# dcy_vca_v1_0_1.net
KiCad netlist of a schematic drawn in EAGLE
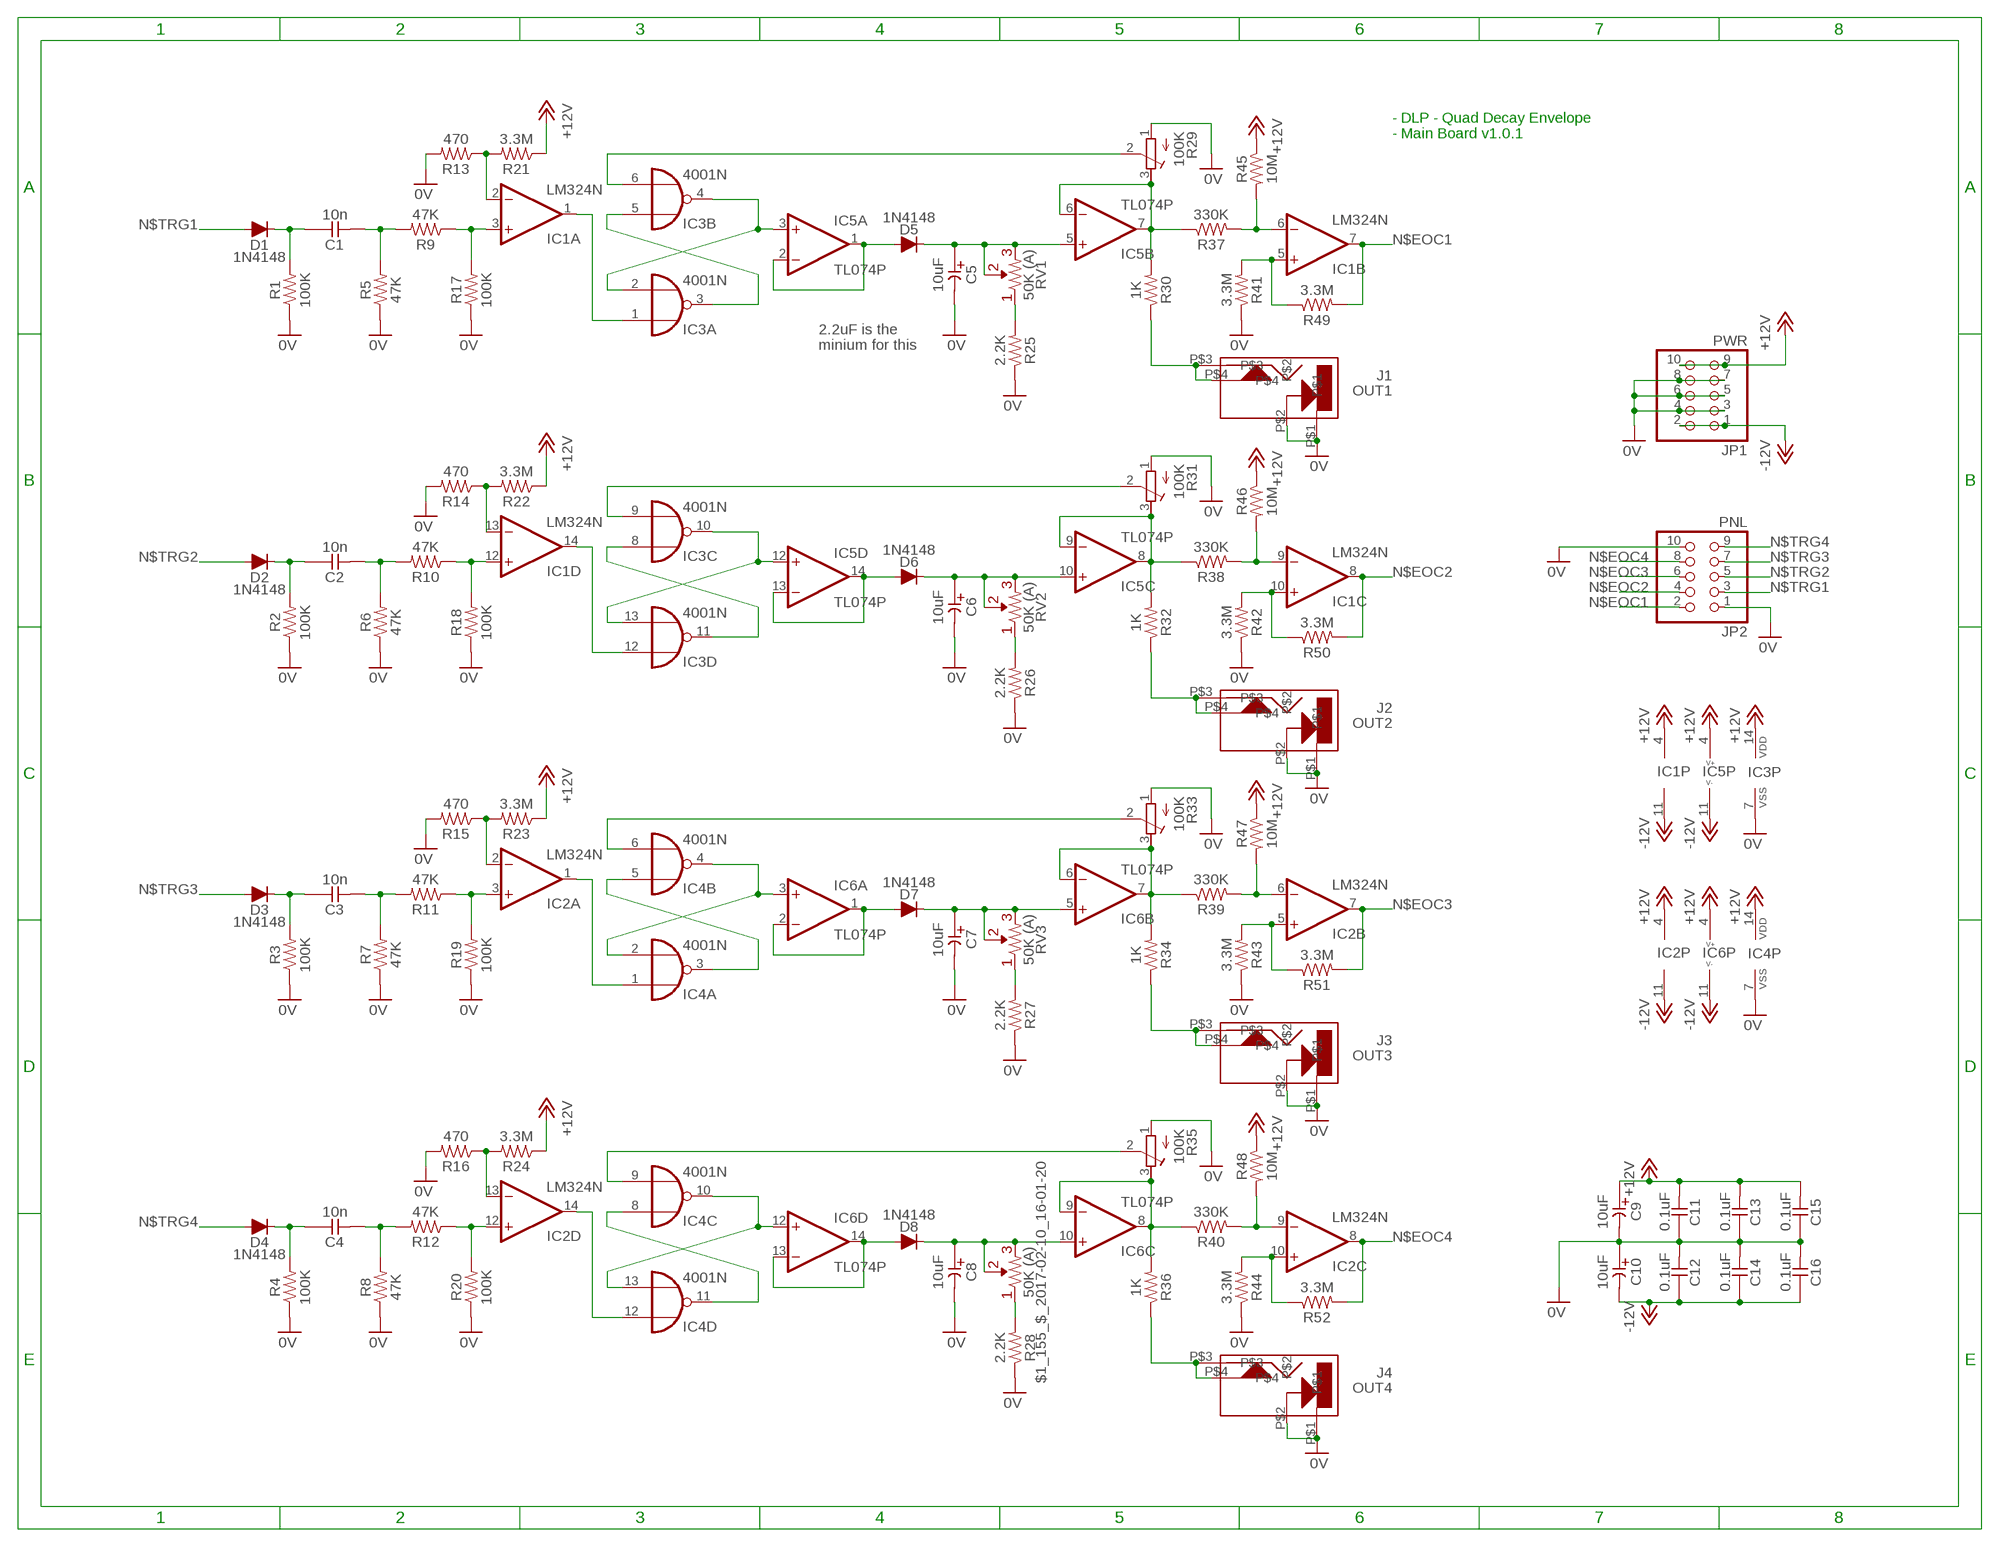
[diagram p0: schematic, sheet 1]

(export (version "E")
  (design (tool "Eeschema 10.0.6"))
  (components
    (comp (ref "$1_155_$_2017-02-10_16-01-20")
      (value "50K (A)")
      (footprint "eagle-import:R-VAR")
      (libsource (lib "eagle-import") (part "R-VAR"))
    )
    (comp (ref "C1")
      (value "10n")
      (footprint "eagle-import:C025-024X044")
      (libsource (lib "eagle-import") (part "CC-US025-024X044"))
    )
    (comp (ref "C2")
      (value "10n")
      (footprint "eagle-import:C025-024X044")
      (libsource (lib "eagle-import") (part "CC-US025-024X044"))
    )
    (comp (ref "C3")
      (value "10n")
      (footprint "eagle-import:C025-024X044")
      (libsource (lib "eagle-import") (part "CC-US025-024X044"))
    )
    (comp (ref "C4")
      (value "10n")
      (footprint "eagle-import:C025-024X044")
      (libsource (lib "eagle-import") (part "CC-US025-024X044"))
    )
    (comp (ref "C5")
      (value "10uF")
      (footprint "eagle-import:E2-5")
      (libsource (lib "eagle-import") (part "CE-USE2-5"))
    )
    (comp (ref "C6")
      (value "10uF")
      (footprint "eagle-import:E2-5")
      (libsource (lib "eagle-import") (part "CE-USE2-5"))
    )
    (comp (ref "C7")
      (value "10uF")
      (footprint "eagle-import:E2-5")
      (libsource (lib "eagle-import") (part "CE-USE2-5"))
    )
    (comp (ref "C8")
      (value "10uF")
      (footprint "eagle-import:E2-5")
      (libsource (lib "eagle-import") (part "CE-USE2-5"))
    )
    (comp (ref "C9")
      (value "10uF")
      (footprint "eagle-import:E2-5")
      (libsource (lib "eagle-import") (part "CE-USE2-5"))
    )
    (comp (ref "C10")
      (value "10uF")
      (footprint "eagle-import:E2-5")
      (libsource (lib "eagle-import") (part "CE-USE2-5"))
    )
    (comp (ref "C11")
      (value "0.1uF")
      (footprint "eagle-import:C025-024X044")
      (libsource (lib "eagle-import") (part "CC-US025-024X044"))
    )
    (comp (ref "C12")
      (value "0.1uF")
      (footprint "eagle-import:C025-024X044")
      (libsource (lib "eagle-import") (part "CC-US025-024X044"))
    )
    (comp (ref "C13")
      (value "0.1uF")
      (footprint "eagle-import:C025-024X044")
      (libsource (lib "eagle-import") (part "CC-US025-024X044"))
    )
    (comp (ref "C14")
      (value "0.1uF")
      (footprint "eagle-import:C025-024X044")
      (libsource (lib "eagle-import") (part "CC-US025-024X044"))
    )
    (comp (ref "C15")
      (value "0.1uF")
      (footprint "eagle-import:C025-024X044")
      (libsource (lib "eagle-import") (part "CC-US025-024X044"))
    )
    (comp (ref "C16")
      (value "0.1uF")
      (footprint "eagle-import:C025-024X044")
      (libsource (lib "eagle-import") (part "CC-US025-024X044"))
    )
    (comp (ref "D1")
      (value "1N4148")
      (footprint "eagle-import:DO34-5")
      (libsource (lib "eagle-import") (part "1N4148"))
    )
    (comp (ref "D2")
      (value "1N4148")
      (footprint "eagle-import:DO34-5")
      (libsource (lib "eagle-import") (part "1N4148"))
    )
    (comp (ref "D3")
      (value "1N4148")
      (footprint "eagle-import:DO34-5")
      (libsource (lib "eagle-import") (part "1N4148"))
    )
    (comp (ref "D4")
      (value "1N4148")
      (footprint "eagle-import:DO34-5")
      (libsource (lib "eagle-import") (part "1N4148"))
    )
    (comp (ref "D5")
      (value "1N4148")
      (footprint "eagle-import:DO34-5")
      (libsource (lib "eagle-import") (part "1N4148"))
    )
    (comp (ref "D6")
      (value "1N4148")
      (footprint "eagle-import:DO34-5")
      (libsource (lib "eagle-import") (part "1N4148"))
    )
    (comp (ref "D7")
      (value "1N4148")
      (footprint "eagle-import:DO34-5")
      (libsource (lib "eagle-import") (part "1N4148"))
    )
    (comp (ref "D8")
      (value "1N4148")
      (footprint "eagle-import:DO34-5")
      (libsource (lib "eagle-import") (part "1N4148"))
    )
    (comp (ref "IC1")
      (value "LM324N")
      (footprint "eagle-import:DIL14")
      (libsource (lib "eagle-import") (part "LM324N"))
    )
    (comp (ref "IC2")
      (value "LM324N")
      (footprint "eagle-import:DIL14")
      (libsource (lib "eagle-import") (part "LM324N"))
    )
    (comp (ref "IC3")
      (value "4001N")
      (footprint "eagle-import:DIL14")
      (libsource (lib "eagle-import") (part "4001N"))
    )
    (comp (ref "IC4")
      (value "4001N")
      (footprint "eagle-import:DIL14")
      (libsource (lib "eagle-import") (part "4001N"))
    )
    (comp (ref "IC5")
      (value "TL074P")
      (footprint "eagle-import:DIL14")
      (libsource (lib "eagle-import") (part "TL074P"))
    )
    (comp (ref "IC6")
      (value "TL074P")
      (footprint "eagle-import:DIL14")
      (libsource (lib "eagle-import") (part "TL074P"))
    )
    (comp (ref "J1")
      (value "OUT1")
      (footprint "eagle-import:CL1384")
      (libsource (lib "eagle-import") (part "CL1384"))
    )
    (comp (ref "J2")
      (value "OUT2")
      (footprint "eagle-import:CL1384")
      (libsource (lib "eagle-import") (part "CL1384"))
    )
    (comp (ref "J3")
      (value "OUT3")
      (footprint "eagle-import:CL1384")
      (libsource (lib "eagle-import") (part "CL1384"))
    )
    (comp (ref "J4")
      (value "OUT4")
      (footprint "eagle-import:CL1384")
      (libsource (lib "eagle-import") (part "CL1384"))
    )
    (comp (ref "JP1")
      (value "PWR")
      (footprint "eagle-import:2X05")
      (libsource (lib "eagle-import") (part "PINHD-2X5"))
    )
    (comp (ref "JP2")
      (value "PNL")
      (footprint "eagle-import:2X05")
      (libsource (lib "eagle-import") (part "PINHD-2X5"))
    )
    (comp (ref "R1")
      (value "100K")
      (footprint "eagle-import:0207_7")
      (libsource (lib "eagle-import") (part "R"))
    )
    (comp (ref "R2")
      (value "100K")
      (footprint "eagle-import:0207_7")
      (libsource (lib "eagle-import") (part "R"))
    )
    (comp (ref "R3")
      (value "100K")
      (footprint "eagle-import:0207_7")
      (libsource (lib "eagle-import") (part "R"))
    )
    (comp (ref "R4")
      (value "100K")
      (footprint "eagle-import:0207_7")
      (libsource (lib "eagle-import") (part "R"))
    )
    (comp (ref "R5")
      (value "47K")
      (footprint "eagle-import:0207_7")
      (libsource (lib "eagle-import") (part "R"))
    )
    (comp (ref "R6")
      (value "47K")
      (footprint "eagle-import:0207_7")
      (libsource (lib "eagle-import") (part "R"))
    )
    (comp (ref "R7")
      (value "47K")
      (footprint "eagle-import:0207_7")
      (libsource (lib "eagle-import") (part "R"))
    )
    (comp (ref "R8")
      (value "47K")
      (footprint "eagle-import:0207_7")
      (libsource (lib "eagle-import") (part "R"))
    )
    (comp (ref "R9")
      (value "47K")
      (footprint "eagle-import:0207_7")
      (libsource (lib "eagle-import") (part "R"))
    )
    (comp (ref "R10")
      (value "47K")
      (footprint "eagle-import:0207_7")
      (libsource (lib "eagle-import") (part "R"))
    )
    (comp (ref "R11")
      (value "47K")
      (footprint "eagle-import:0207_7")
      (libsource (lib "eagle-import") (part "R"))
    )
    (comp (ref "R12")
      (value "47K")
      (footprint "eagle-import:0207_7")
      (libsource (lib "eagle-import") (part "R"))
    )
    (comp (ref "R13")
      (value "470")
      (footprint "eagle-import:0207_7")
      (libsource (lib "eagle-import") (part "R"))
    )
    (comp (ref "R14")
      (value "470")
      (footprint "eagle-import:0207_7")
      (libsource (lib "eagle-import") (part "R"))
    )
    (comp (ref "R15")
      (value "470")
      (footprint "eagle-import:0207_7")
      (libsource (lib "eagle-import") (part "R"))
    )
    (comp (ref "R16")
      (value "470")
      (footprint "eagle-import:0207_7")
      (libsource (lib "eagle-import") (part "R"))
    )
    (comp (ref "R17")
      (value "100K")
      (footprint "eagle-import:0207_7")
      (libsource (lib "eagle-import") (part "R"))
    )
    (comp (ref "R18")
      (value "100K")
      (footprint "eagle-import:0207_7")
      (libsource (lib "eagle-import") (part "R"))
    )
    (comp (ref "R19")
      (value "100K")
      (footprint "eagle-import:0207_7")
      (libsource (lib "eagle-import") (part "R"))
    )
    (comp (ref "R20")
      (value "100K")
      (footprint "eagle-import:0207_7")
      (libsource (lib "eagle-import") (part "R"))
    )
    (comp (ref "R21")
      (value "3.3M")
      (footprint "eagle-import:0207_7")
      (libsource (lib "eagle-import") (part "R"))
    )
    (comp (ref "R22")
      (value "3.3M")
      (footprint "eagle-import:0207_7")
      (libsource (lib "eagle-import") (part "R"))
    )
    (comp (ref "R23")
      (value "3.3M")
      (footprint "eagle-import:0207_7")
      (libsource (lib "eagle-import") (part "R"))
    )
    (comp (ref "R24")
      (value "3.3M")
      (footprint "eagle-import:0207_7")
      (libsource (lib "eagle-import") (part "R"))
    )
    (comp (ref "R25")
      (value "2.2K")
      (footprint "eagle-import:0207_7")
      (libsource (lib "eagle-import") (part "R"))
    )
    (comp (ref "R26")
      (value "2.2K")
      (footprint "eagle-import:0207_7")
      (libsource (lib "eagle-import") (part "R"))
    )
    (comp (ref "R27")
      (value "2.2K")
      (footprint "eagle-import:0207_7")
      (libsource (lib "eagle-import") (part "R"))
    )
    (comp (ref "R28")
      (value "2.2K")
      (footprint "eagle-import:0207_7")
      (libsource (lib "eagle-import") (part "R"))
    )
    (comp (ref "R29")
      (value "100K")
      (footprint "eagle-import:RTRIM3339P")
      (libsource (lib "eagle-import") (part "R-TRIMM3339P"))
    )
    (comp (ref "R30")
      (value "1K")
      (footprint "eagle-import:0207_7")
      (libsource (lib "eagle-import") (part "R"))
    )
    (comp (ref "R31")
      (value "100K")
      (footprint "eagle-import:RTRIM3339P")
      (libsource (lib "eagle-import") (part "R-TRIMM3339P"))
    )
    (comp (ref "R32")
      (value "1K")
      (footprint "eagle-import:0207_7")
      (libsource (lib "eagle-import") (part "R"))
    )
    (comp (ref "R33")
      (value "100K")
      (footprint "eagle-import:RTRIM3339P")
      (libsource (lib "eagle-import") (part "R-TRIMM3339P"))
    )
    (comp (ref "R34")
      (value "1K")
      (footprint "eagle-import:0207_7")
      (libsource (lib "eagle-import") (part "R"))
    )
    (comp (ref "R35")
      (value "100K")
      (footprint "eagle-import:RTRIM3339P")
      (libsource (lib "eagle-import") (part "R-TRIMM3339P"))
    )
    (comp (ref "R36")
      (value "1K")
      (footprint "eagle-import:0207_7")
      (libsource (lib "eagle-import") (part "R"))
    )
    (comp (ref "R37")
      (value "330K")
      (footprint "eagle-import:0207_7")
      (libsource (lib "eagle-import") (part "R"))
    )
    (comp (ref "R38")
      (value "330K")
      (footprint "eagle-import:0207_7")
      (libsource (lib "eagle-import") (part "R"))
    )
    (comp (ref "R39")
      (value "330K")
      (footprint "eagle-import:0207_7")
      (libsource (lib "eagle-import") (part "R"))
    )
    (comp (ref "R40")
      (value "330K")
      (footprint "eagle-import:0207_7")
      (libsource (lib "eagle-import") (part "R"))
    )
    (comp (ref "R41")
      (value "3.3M")
      (footprint "eagle-import:0207_7")
      (libsource (lib "eagle-import") (part "R"))
    )
    (comp (ref "R42")
      (value "3.3M")
      (footprint "eagle-import:0207_7")
      (libsource (lib "eagle-import") (part "R"))
    )
    (comp (ref "R43")
      (value "3.3M")
      (footprint "eagle-import:0207_7")
      (libsource (lib "eagle-import") (part "R"))
    )
    (comp (ref "R44")
      (value "3.3M")
      (footprint "eagle-import:0207_7")
      (libsource (lib "eagle-import") (part "R"))
    )
    (comp (ref "R45")
      (value "10M")
      (footprint "eagle-import:0207_7")
      (libsource (lib "eagle-import") (part "R"))
    )
    (comp (ref "R46")
      (value "10M")
      (footprint "eagle-import:0207_7")
      (libsource (lib "eagle-import") (part "R"))
    )
    (comp (ref "R47")
      (value "10M")
      (footprint "eagle-import:0207_7")
      (libsource (lib "eagle-import") (part "R"))
    )
    (comp (ref "R48")
      (value "10M")
      (footprint "eagle-import:0207_7")
      (libsource (lib "eagle-import") (part "R"))
    )
    (comp (ref "R49")
      (value "3.3M")
      (footprint "eagle-import:0207_7")
      (libsource (lib "eagle-import") (part "R"))
    )
    (comp (ref "R50")
      (value "3.3M")
      (footprint "eagle-import:0207_7")
      (libsource (lib "eagle-import") (part "R"))
    )
    (comp (ref "R51")
      (value "3.3M")
      (footprint "eagle-import:0207_7")
      (libsource (lib "eagle-import") (part "R"))
    )
    (comp (ref "R52")
      (value "3.3M")
      (footprint "eagle-import:0207_7")
      (libsource (lib "eagle-import") (part "R"))
    )
    (comp (ref "RV1")
      (value "50K (A)")
      (footprint "eagle-import:R-VAR")
      (libsource (lib "eagle-import") (part "R-VAR"))
    )
    (comp (ref "RV2")
      (value "50K (A)")
      (footprint "eagle-import:R-VAR")
      (libsource (lib "eagle-import") (part "R-VAR"))
    )
    (comp (ref "RV3")
      (value "50K (A)")
      (footprint "eagle-import:R-VAR")
      (libsource (lib "eagle-import") (part "R-VAR"))
    )
  )
  (nets
    (net (code "1") (name "+12V") (class "Default")
      (node (ref "C11") (pin "2") (pinfunction "2_2") (pintype "passive"))
      (node (ref "C13") (pin "2") (pinfunction "2_2") (pintype "passive"))
      (node (ref "C15") (pin "2") (pinfunction "2_2") (pintype "passive"))
      (node (ref "C9") (pin "+") (pinfunction "+_+") (pintype "passive"))
      (node (ref "IC1") (pin "4") (pinfunction "V+_4") (pintype "power_in"))
      (node (ref "IC2") (pin "4") (pinfunction "V+_4") (pintype "power_in"))
      (node (ref "IC3") (pin "14") (pinfunction "VDD_14") (pintype "power_in"))
      (node (ref "IC4") (pin "14") (pinfunction "VDD_14") (pintype "power_in"))
      (node (ref "IC5") (pin "4") (pinfunction "V+_4") (pintype "power_in"))
      (node (ref "IC6") (pin "4") (pinfunction "V+_4") (pintype "power_in"))
      (node (ref "JP1") (pin "10") (pinfunction "10_10") (pintype "passive"))
      (node (ref "JP1") (pin "9") (pinfunction "9_9") (pintype "passive"))
      (node (ref "R21") (pin "1") (pinfunction "1_1") (pintype "passive"))
      (node (ref "R22") (pin "1") (pinfunction "1_1") (pintype "passive"))
      (node (ref "R23") (pin "1") (pinfunction "1_1") (pintype "passive"))
      (node (ref "R24") (pin "1") (pinfunction "1_1") (pintype "passive"))
      (node (ref "R45") (pin "1") (pinfunction "1_1") (pintype "passive"))
      (node (ref "R46") (pin "1") (pinfunction "1_1") (pintype "passive"))
      (node (ref "R47") (pin "1") (pinfunction "1_1") (pintype "passive"))
      (node (ref "R48") (pin "1") (pinfunction "1_1") (pintype "passive"))
    )
    (net (code "2") (name "-12V") (class "Default")
      (node (ref "C10") (pin "-") (pinfunction "-_-") (pintype "passive"))
      (node (ref "C12") (pin "1") (pinfunction "1_1") (pintype "passive"))
      (node (ref "C14") (pin "1") (pinfunction "1_1") (pintype "passive"))
      (node (ref "C16") (pin "1") (pinfunction "1_1") (pintype "passive"))
      (node (ref "IC1") (pin "11") (pinfunction "V-_11") (pintype "power_in"))
      (node (ref "IC2") (pin "11") (pinfunction "V-_11") (pintype "power_in"))
      (node (ref "IC5") (pin "11") (pinfunction "V-_11") (pintype "power_in"))
      (node (ref "IC6") (pin "11") (pinfunction "V-_11") (pintype "power_in"))
      (node (ref "JP1") (pin "1") (pinfunction "1_1") (pintype "passive"))
      (node (ref "JP1") (pin "2") (pinfunction "2_2") (pintype "passive"))
    )
    (net (code "3") (name "/N$EOC1") (class "Default")
      (node (ref "IC1") (pin "7") (pinfunction "OUT_7") (pintype "output"))
      (node (ref "JP2") (pin "2") (pinfunction "2_2") (pintype "passive"))
      (node (ref "R49") (pin "2") (pinfunction "2_2") (pintype "passive"))
    )
    (net (code "4") (name "/N$EOC2") (class "Default")
      (node (ref "IC1") (pin "8") (pinfunction "OUT_8") (pintype "output"))
      (node (ref "JP2") (pin "4") (pinfunction "4_4") (pintype "passive"))
      (node (ref "R50") (pin "2") (pinfunction "2_2") (pintype "passive"))
    )
    (net (code "5") (name "/N$EOC3") (class "Default")
      (node (ref "IC2") (pin "7") (pinfunction "OUT_7") (pintype "output"))
      (node (ref "JP2") (pin "6") (pinfunction "6_6") (pintype "passive"))
      (node (ref "R51") (pin "2") (pinfunction "2_2") (pintype "passive"))
    )
    (net (code "6") (name "/N$EOC4") (class "Default")
      (node (ref "IC2") (pin "8") (pinfunction "OUT_8") (pintype "output"))
      (node (ref "JP2") (pin "8") (pinfunction "8_8") (pintype "passive"))
      (node (ref "R52") (pin "2") (pinfunction "2_2") (pintype "passive"))
    )
    (net (code "7") (name "/N$TRG1") (class "Default")
      (node (ref "D1") (pin "A") (pinfunction "A_A") (pintype "passive"))
      (node (ref "JP2") (pin "3") (pinfunction "3_3") (pintype "passive"))
    )
    (net (code "8") (name "/N$TRG2") (class "Default")
      (node (ref "D2") (pin "A") (pinfunction "A_A") (pintype "passive"))
      (node (ref "JP2") (pin "5") (pinfunction "5_5") (pintype "passive"))
    )
    (net (code "9") (name "/N$TRG3") (class "Default")
      (node (ref "D3") (pin "A") (pinfunction "A_A") (pintype "passive"))
      (node (ref "JP2") (pin "7") (pinfunction "7_7") (pintype "passive"))
    )
    (net (code "10") (name "/N$TRG4") (class "Default")
      (node (ref "D4") (pin "A") (pinfunction "A_A") (pintype "passive"))
      (node (ref "JP2") (pin "9") (pinfunction "9_9") (pintype "passive"))
    )
    (net (code "11") (name "0V") (class "Default")
      (node (ref "C10") (pin "+") (pinfunction "+_+") (pintype "passive"))
      (node (ref "C11") (pin "1") (pinfunction "1_1") (pintype "passive"))
      (node (ref "C12") (pin "2") (pinfunction "2_2") (pintype "passive"))
      (node (ref "C13") (pin "1") (pinfunction "1_1") (pintype "passive"))
      (node (ref "C14") (pin "2") (pinfunction "2_2") (pintype "passive"))
      (node (ref "C15") (pin "1") (pinfunction "1_1") (pintype "passive"))
      (node (ref "C16") (pin "2") (pinfunction "2_2") (pintype "passive"))
      (node (ref "C5") (pin "-") (pinfunction "-_-") (pintype "passive"))
      (node (ref "C6") (pin "-") (pinfunction "-_-") (pintype "passive"))
      (node (ref "C7") (pin "-") (pinfunction "-_-") (pintype "passive"))
      (node (ref "C8") (pin "-") (pinfunction "-_-") (pintype "passive"))
      (node (ref "C9") (pin "-") (pinfunction "-_-") (pintype "passive"))
      (node (ref "IC3") (pin "7") (pinfunction "VSS_7") (pintype "power_in"))
      (node (ref "IC4") (pin "7") (pinfunction "VSS_7") (pintype "power_in"))
      (node (ref "J1") (pin "P$1") (pinfunction "P$1_P$1") (pintype "bidirectional"))
      (node (ref "J1") (pin "P$2") (pinfunction "P$2_P$2") (pintype "bidirectional"))
      (node (ref "J2") (pin "P$1") (pinfunction "P$1_P$1") (pintype "bidirectional"))
      (node (ref "J2") (pin "P$2") (pinfunction "P$2_P$2") (pintype "bidirectional"))
      (node (ref "J3") (pin "P$1") (pinfunction "P$1_P$1") (pintype "bidirectional"))
      (node (ref "J3") (pin "P$2") (pinfunction "P$2_P$2") (pintype "bidirectional"))
      (node (ref "J4") (pin "P$1") (pinfunction "P$1_P$1") (pintype "bidirectional"))
      (node (ref "J4") (pin "P$2") (pinfunction "P$2_P$2") (pintype "bidirectional"))
      (node (ref "JP1") (pin "3") (pinfunction "3_3") (pintype "passive"))
      (node (ref "JP1") (pin "4") (pinfunction "4_4") (pintype "passive"))
      (node (ref "JP1") (pin "5") (pinfunction "5_5") (pintype "passive"))
      (node (ref "JP1") (pin "6") (pinfunction "6_6") (pintype "passive"))
      (node (ref "JP1") (pin "7") (pinfunction "7_7") (pintype "passive"))
      (node (ref "JP1") (pin "8") (pinfunction "8_8") (pintype "passive"))
      (node (ref "JP2") (pin "1") (pinfunction "1_1") (pintype "passive"))
      (node (ref "JP2") (pin "10") (pinfunction "10_10") (pintype "passive"))
      (node (ref "R1") (pin "1") (pinfunction "1_1") (pintype "passive"))
      (node (ref "R13") (pin "2") (pinfunction "2_2") (pintype "passive"))
      (node (ref "R14") (pin "2") (pinfunction "2_2") (pintype "passive"))
      (node (ref "R15") (pin "2") (pinfunction "2_2") (pintype "passive"))
      (node (ref "R16") (pin "2") (pinfunction "2_2") (pintype "passive"))
      (node (ref "R17") (pin "1") (pinfunction "1_1") (pintype "passive"))
      (node (ref "R18") (pin "1") (pinfunction "1_1") (pintype "passive"))
      (node (ref "R19") (pin "1") (pinfunction "1_1") (pintype "passive"))
      (node (ref "R2") (pin "1") (pinfunction "1_1") (pintype "passive"))
      (node (ref "R20") (pin "1") (pinfunction "1_1") (pintype "passive"))
      (node (ref "R25") (pin "1") (pinfunction "1_1") (pintype "passive"))
      (node (ref "R26") (pin "1") (pinfunction "1_1") (pintype "passive"))
      (node (ref "R27") (pin "1") (pinfunction "1_1") (pintype "passive"))
      (node (ref "R28") (pin "1") (pinfunction "1_1") (pintype "passive"))
      (node (ref "R29") (pin "1") (pinfunction "A_1") (pintype "passive"))
      (node (ref "R3") (pin "1") (pinfunction "1_1") (pintype "passive"))
      (node (ref "R31") (pin "1") (pinfunction "A_1") (pintype "passive"))
      (node (ref "R33") (pin "1") (pinfunction "A_1") (pintype "passive"))
      (node (ref "R35") (pin "1") (pinfunction "A_1") (pintype "passive"))
      (node (ref "R4") (pin "1") (pinfunction "1_1") (pintype "passive"))
      (node (ref "R41") (pin "1") (pinfunction "1_1") (pintype "passive"))
      (node (ref "R42") (pin "1") (pinfunction "1_1") (pintype "passive"))
      (node (ref "R43") (pin "1") (pinfunction "1_1") (pintype "passive"))
      (node (ref "R44") (pin "1") (pinfunction "1_1") (pintype "passive"))
      (node (ref "R5") (pin "1") (pinfunction "1_1") (pintype "passive"))
      (node (ref "R6") (pin "1") (pinfunction "1_1") (pintype "passive"))
      (node (ref "R7") (pin "1") (pinfunction "1_1") (pintype "passive"))
      (node (ref "R8") (pin "1") (pinfunction "1_1") (pintype "passive"))
    )
    (net (code "12") (name "Net-($1_155_$_2017-02-10_16-01-20-1)") (class "Default")
      (node (ref "$1_155_$_2017-02-10_16-01-20") (pin "R1") (pinfunction "1_R1") (pintype "passive"))
      (node (ref "R28") (pin "2") (pinfunction "2_2") (pintype "passive"))
    )
    (net (code "13") (name "Net-($1_155_$_2017-02-10_16-01-20-2)") (class "Default")
      (node (ref "$1_155_$_2017-02-10_16-01-20") (pin "R2") (pinfunction "2_R2") (pintype "passive"))
      (node (ref "$1_155_$_2017-02-10_16-01-20") (pin "VAR") (pinfunction "P$1_VAR") (pintype "passive"))
      (node (ref "C8") (pin "+") (pinfunction "+_+") (pintype "passive"))
      (node (ref "D8") (pin "C") (pinfunction "C_C") (pintype "passive"))
      (node (ref "IC6") (pin "10") (pinfunction "+IN_10") (pintype "input"))
    )
    (net (code "14") (name "Net-(C1-Pad1)") (class "Default")
      (node (ref "C1") (pin "1") (pinfunction "1_1") (pintype "passive"))
      (node (ref "D1") (pin "C") (pinfunction "C_C") (pintype "passive"))
      (node (ref "R1") (pin "2") (pinfunction "2_2") (pintype "passive"))
    )
    (net (code "15") (name "Net-(C1-Pad2)") (class "Default")
      (node (ref "C1") (pin "2") (pinfunction "2_2") (pintype "passive"))
      (node (ref "R5") (pin "2") (pinfunction "2_2") (pintype "passive"))
      (node (ref "R9") (pin "2") (pinfunction "2_2") (pintype "passive"))
    )
    (net (code "16") (name "Net-(C2-Pad1)") (class "Default")
      (node (ref "C2") (pin "1") (pinfunction "1_1") (pintype "passive"))
      (node (ref "D2") (pin "C") (pinfunction "C_C") (pintype "passive"))
      (node (ref "R2") (pin "2") (pinfunction "2_2") (pintype "passive"))
    )
    (net (code "17") (name "Net-(C2-Pad2)") (class "Default")
      (node (ref "C2") (pin "2") (pinfunction "2_2") (pintype "passive"))
      (node (ref "R10") (pin "2") (pinfunction "2_2") (pintype "passive"))
      (node (ref "R6") (pin "2") (pinfunction "2_2") (pintype "passive"))
    )
    (net (code "18") (name "Net-(C3-Pad1)") (class "Default")
      (node (ref "C3") (pin "1") (pinfunction "1_1") (pintype "passive"))
      (node (ref "D3") (pin "C") (pinfunction "C_C") (pintype "passive"))
      (node (ref "R3") (pin "2") (pinfunction "2_2") (pintype "passive"))
    )
    (net (code "19") (name "Net-(C3-Pad2)") (class "Default")
      (node (ref "C3") (pin "2") (pinfunction "2_2") (pintype "passive"))
      (node (ref "R11") (pin "2") (pinfunction "2_2") (pintype "passive"))
      (node (ref "R7") (pin "2") (pinfunction "2_2") (pintype "passive"))
    )
    (net (code "20") (name "Net-(C4-Pad1)") (class "Default")
      (node (ref "C4") (pin "1") (pinfunction "1_1") (pintype "passive"))
      (node (ref "D4") (pin "C") (pinfunction "C_C") (pintype "passive"))
      (node (ref "R4") (pin "2") (pinfunction "2_2") (pintype "passive"))
    )
    (net (code "21") (name "Net-(C4-Pad2)") (class "Default")
      (node (ref "C4") (pin "2") (pinfunction "2_2") (pintype "passive"))
      (node (ref "R12") (pin "2") (pinfunction "2_2") (pintype "passive"))
      (node (ref "R8") (pin "2") (pinfunction "2_2") (pintype "passive"))
    )
    (net (code "22") (name "Net-(IC1A-+IN)") (class "Default")
      (node (ref "IC1") (pin "3") (pinfunction "+IN_3") (pintype "input"))
      (node (ref "R17") (pin "2") (pinfunction "2_2") (pintype "passive"))
      (node (ref "R9") (pin "1") (pinfunction "1_1") (pintype "passive"))
    )
    (net (code "23") (name "Net-(IC1A--IN)") (class "Default")
      (node (ref "IC1") (pin "2") (pinfunction "-IN_2") (pintype "input"))
      (node (ref "R13") (pin "1") (pinfunction "1_1") (pintype "passive"))
      (node (ref "R21") (pin "2") (pinfunction "2_2") (pintype "passive"))
    )
    (net (code "24") (name "Net-(IC1A-OUT)") (class "Default")
      (node (ref "IC1") (pin "1") (pinfunction "OUT_1") (pintype "output"))
      (node (ref "IC3") (pin "1") (pinfunction "I0_1") (pintype "input"))
    )
    (net (code "25") (name "Net-(IC1B-+IN)") (class "Default")
      (node (ref "IC1") (pin "5") (pinfunction "+IN_5") (pintype "input"))
      (node (ref "R41") (pin "2") (pinfunction "2_2") (pintype "passive"))
      (node (ref "R49") (pin "1") (pinfunction "1_1") (pintype "passive"))
    )
    (net (code "26") (name "Net-(IC1B--IN)") (class "Default")
      (node (ref "IC1") (pin "6") (pinfunction "-IN_6") (pintype "input"))
      (node (ref "R37") (pin "2") (pinfunction "2_2") (pintype "passive"))
      (node (ref "R45") (pin "2") (pinfunction "2_2") (pintype "passive"))
    )
    (net (code "27") (name "Net-(IC1C-+IN)") (class "Default")
      (node (ref "IC1") (pin "10") (pinfunction "+IN_10") (pintype "input"))
      (node (ref "R42") (pin "2") (pinfunction "2_2") (pintype "passive"))
      (node (ref "R50") (pin "1") (pinfunction "1_1") (pintype "passive"))
    )
    (net (code "28") (name "Net-(IC1C--IN)") (class "Default")
      (node (ref "IC1") (pin "9") (pinfunction "-IN_9") (pintype "input"))
      (node (ref "R38") (pin "2") (pinfunction "2_2") (pintype "passive"))
      (node (ref "R46") (pin "2") (pinfunction "2_2") (pintype "passive"))
    )
    (net (code "29") (name "Net-(IC1D-+IN)") (class "Default")
      (node (ref "IC1") (pin "12") (pinfunction "+IN_12") (pintype "input"))
      (node (ref "R10") (pin "1") (pinfunction "1_1") (pintype "passive"))
      (node (ref "R18") (pin "2") (pinfunction "2_2") (pintype "passive"))
    )
    (net (code "30") (name "Net-(IC1D--IN)") (class "Default")
      (node (ref "IC1") (pin "13") (pinfunction "-IN_13") (pintype "input"))
      (node (ref "R14") (pin "1") (pinfunction "1_1") (pintype "passive"))
      (node (ref "R22") (pin "2") (pinfunction "2_2") (pintype "passive"))
    )
    (net (code "31") (name "Net-(IC1D-OUT)") (class "Default")
      (node (ref "IC1") (pin "14") (pinfunction "OUT_14") (pintype "output"))
      (node (ref "IC3") (pin "12") (pinfunction "I0_12") (pintype "input"))
    )
    (net (code "32") (name "Net-(IC2A-+IN)") (class "Default")
      (node (ref "IC2") (pin "3") (pinfunction "+IN_3") (pintype "input"))
      (node (ref "R11") (pin "1") (pinfunction "1_1") (pintype "passive"))
      (node (ref "R19") (pin "2") (pinfunction "2_2") (pintype "passive"))
    )
    (net (code "33") (name "Net-(IC2A--IN)") (class "Default")
      (node (ref "IC2") (pin "2") (pinfunction "-IN_2") (pintype "input"))
      (node (ref "R15") (pin "1") (pinfunction "1_1") (pintype "passive"))
      (node (ref "R23") (pin "2") (pinfunction "2_2") (pintype "passive"))
    )
    (net (code "34") (name "Net-(IC2A-OUT)") (class "Default")
      (node (ref "IC2") (pin "1") (pinfunction "OUT_1") (pintype "output"))
      (node (ref "IC4") (pin "1") (pinfunction "I0_1") (pintype "input"))
    )
    (net (code "35") (name "Net-(IC2B-+IN)") (class "Default")
      (node (ref "IC2") (pin "5") (pinfunction "+IN_5") (pintype "input"))
      (node (ref "R43") (pin "2") (pinfunction "2_2") (pintype "passive"))
      (node (ref "R51") (pin "1") (pinfunction "1_1") (pintype "passive"))
    )
    (net (code "36") (name "Net-(IC2B--IN)") (class "Default")
      (node (ref "IC2") (pin "6") (pinfunction "-IN_6") (pintype "input"))
      (node (ref "R39") (pin "2") (pinfunction "2_2") (pintype "passive"))
      (node (ref "R47") (pin "2") (pinfunction "2_2") (pintype "passive"))
    )
    (net (code "37") (name "Net-(IC2C-+IN)") (class "Default")
      (node (ref "IC2") (pin "10") (pinfunction "+IN_10") (pintype "input"))
      (node (ref "R44") (pin "2") (pinfunction "2_2") (pintype "passive"))
      (node (ref "R52") (pin "1") (pinfunction "1_1") (pintype "passive"))
    )
    (net (code "38") (name "Net-(IC2C--IN)") (class "Default")
      (node (ref "IC2") (pin "9") (pinfunction "-IN_9") (pintype "input"))
      (node (ref "R40") (pin "2") (pinfunction "2_2") (pintype "passive"))
      (node (ref "R48") (pin "2") (pinfunction "2_2") (pintype "passive"))
    )
    (net (code "39") (name "Net-(IC2D-+IN)") (class "Default")
      (node (ref "IC2") (pin "12") (pinfunction "+IN_12") (pintype "input"))
      (node (ref "R12") (pin "1") (pinfunction "1_1") (pintype "passive"))
      (node (ref "R20") (pin "2") (pinfunction "2_2") (pintype "passive"))
    )
    (net (code "40") (name "Net-(IC2D--IN)") (class "Default")
      (node (ref "IC2") (pin "13") (pinfunction "-IN_13") (pintype "input"))
      (node (ref "R16") (pin "1") (pinfunction "1_1") (pintype "passive"))
      (node (ref "R24") (pin "2") (pinfunction "2_2") (pintype "passive"))
    )
    (net (code "41") (name "Net-(IC2D-OUT)") (class "Default")
      (node (ref "IC2") (pin "14") (pinfunction "OUT_14") (pintype "output"))
      (node (ref "IC4") (pin "12") (pinfunction "I0_12") (pintype "input"))
    )
    (net (code "42") (name "Net-(IC3A-I1)") (class "Default")
      (node (ref "IC3") (pin "2") (pinfunction "I1_2") (pintype "input"))
      (node (ref "IC3") (pin "4") (pinfunction "O_4") (pintype "output"))
      (node (ref "IC5") (pin "3") (pinfunction "+IN_3") (pintype "input"))
    )
    (net (code "43") (name "Net-(IC3A-O)") (class "Default")
      (node (ref "IC3") (pin "3") (pinfunction "O_3") (pintype "output"))
      (node (ref "IC3") (pin "5") (pinfunction "I0_5") (pintype "input"))
    )
    (net (code "44") (name "Net-(IC3B-I1)") (class "Default")
      (node (ref "IC3") (pin "6") (pinfunction "I1_6") (pintype "input"))
      (node (ref "R29") (pin "2") (pinfunction "S_2") (pintype "passive"))
    )
    (net (code "45") (name "Net-(IC3C-I0)") (class "Default")
      (node (ref "IC3") (pin "11") (pinfunction "O_11") (pintype "output"))
      (node (ref "IC3") (pin "8") (pinfunction "I0_8") (pintype "input"))
    )
    (net (code "46") (name "Net-(IC3C-I1)") (class "Default")
      (node (ref "IC3") (pin "9") (pinfunction "I1_9") (pintype "input"))
      (node (ref "R31") (pin "2") (pinfunction "S_2") (pintype "passive"))
    )
    (net (code "47") (name "Net-(IC3C-O)") (class "Default")
      (node (ref "IC3") (pin "10") (pinfunction "O_10") (pintype "output"))
      (node (ref "IC3") (pin "13") (pinfunction "I1_13") (pintype "input"))
      (node (ref "IC5") (pin "12") (pinfunction "+IN_12") (pintype "input"))
    )
    (net (code "48") (name "Net-(IC4A-I1)") (class "Default")
      (node (ref "IC4") (pin "2") (pinfunction "I1_2") (pintype "input"))
      (node (ref "IC4") (pin "4") (pinfunction "O_4") (pintype "output"))
      (node (ref "IC6") (pin "3") (pinfunction "+IN_3") (pintype "input"))
    )
    (net (code "49") (name "Net-(IC4A-O)") (class "Default")
      (node (ref "IC4") (pin "3") (pinfunction "O_3") (pintype "output"))
      (node (ref "IC4") (pin "5") (pinfunction "I0_5") (pintype "input"))
    )
    (net (code "50") (name "Net-(IC4B-I1)") (class "Default")
      (node (ref "IC4") (pin "6") (pinfunction "I1_6") (pintype "input"))
      (node (ref "R33") (pin "2") (pinfunction "S_2") (pintype "passive"))
    )
    (net (code "51") (name "Net-(IC4C-I0)") (class "Default")
      (node (ref "IC4") (pin "11") (pinfunction "O_11") (pintype "output"))
      (node (ref "IC4") (pin "8") (pinfunction "I0_8") (pintype "input"))
    )
    (net (code "52") (name "Net-(IC4C-I1)") (class "Default")
      (node (ref "IC4") (pin "9") (pinfunction "I1_9") (pintype "input"))
      (node (ref "R35") (pin "2") (pinfunction "S_2") (pintype "passive"))
    )
    (net (code "53") (name "Net-(IC4C-O)") (class "Default")
      (node (ref "IC4") (pin "10") (pinfunction "O_10") (pintype "output"))
      (node (ref "IC4") (pin "13") (pinfunction "I1_13") (pintype "input"))
      (node (ref "IC6") (pin "12") (pinfunction "+IN_12") (pintype "input"))
    )
    (net (code "54") (name "Net-(IC5A--IN)") (class "Default")
      (node (ref "D5") (pin "A") (pinfunction "A_A") (pintype "passive"))
      (node (ref "IC5") (pin "1") (pinfunction "OUT_1") (pintype "output"))
      (node (ref "IC5") (pin "2") (pinfunction "-IN_2") (pintype "input"))
    )
    (net (code "55") (name "Net-(IC5B-+IN)") (class "Default")
      (node (ref "C5") (pin "+") (pinfunction "+_+") (pintype "passive"))
      (node (ref "D5") (pin "C") (pinfunction "C_C") (pintype "passive"))
      (node (ref "IC5") (pin "5") (pinfunction "+IN_5") (pintype "input"))
      (node (ref "RV1") (pin "R2") (pinfunction "2_R2") (pintype "passive"))
      (node (ref "RV1") (pin "VAR") (pinfunction "P$1_VAR") (pintype "passive"))
    )
    (net (code "56") (name "Net-(IC5B--IN)") (class "Default")
      (node (ref "IC5") (pin "6") (pinfunction "-IN_6") (pintype "input"))
      (node (ref "IC5") (pin "7") (pinfunction "OUT_7") (pintype "output"))
      (node (ref "R29") (pin "3") (pinfunction "E_3") (pintype "passive"))
      (node (ref "R30") (pin "2") (pinfunction "2_2") (pintype "passive"))
      (node (ref "R37") (pin "1") (pinfunction "1_1") (pintype "passive"))
    )
    (net (code "57") (name "Net-(IC5C-+IN)") (class "Default")
      (node (ref "C6") (pin "+") (pinfunction "+_+") (pintype "passive"))
      (node (ref "D6") (pin "C") (pinfunction "C_C") (pintype "passive"))
      (node (ref "IC5") (pin "10") (pinfunction "+IN_10") (pintype "input"))
      (node (ref "RV2") (pin "R2") (pinfunction "2_R2") (pintype "passive"))
      (node (ref "RV2") (pin "VAR") (pinfunction "P$1_VAR") (pintype "passive"))
    )
    (net (code "58") (name "Net-(IC5C--IN)") (class "Default")
      (node (ref "IC5") (pin "8") (pinfunction "OUT_8") (pintype "output"))
      (node (ref "IC5") (pin "9") (pinfunction "-IN_9") (pintype "input"))
      (node (ref "R31") (pin "3") (pinfunction "E_3") (pintype "passive"))
      (node (ref "R32") (pin "2") (pinfunction "2_2") (pintype "passive"))
      (node (ref "R38") (pin "1") (pinfunction "1_1") (pintype "passive"))
    )
    (net (code "59") (name "Net-(IC5D--IN)") (class "Default")
      (node (ref "D6") (pin "A") (pinfunction "A_A") (pintype "passive"))
      (node (ref "IC5") (pin "13") (pinfunction "-IN_13") (pintype "input"))
      (node (ref "IC5") (pin "14") (pinfunction "OUT_14") (pintype "output"))
    )
    (net (code "60") (name "Net-(IC6A--IN)") (class "Default")
      (node (ref "D7") (pin "A") (pinfunction "A_A") (pintype "passive"))
      (node (ref "IC6") (pin "1") (pinfunction "OUT_1") (pintype "output"))
      (node (ref "IC6") (pin "2") (pinfunction "-IN_2") (pintype "input"))
    )
    (net (code "61") (name "Net-(IC6B-+IN)") (class "Default")
      (node (ref "C7") (pin "+") (pinfunction "+_+") (pintype "passive"))
      (node (ref "D7") (pin "C") (pinfunction "C_C") (pintype "passive"))
      (node (ref "IC6") (pin "5") (pinfunction "+IN_5") (pintype "input"))
      (node (ref "RV3") (pin "R2") (pinfunction "2_R2") (pintype "passive"))
      (node (ref "RV3") (pin "VAR") (pinfunction "P$1_VAR") (pintype "passive"))
    )
    (net (code "62") (name "Net-(IC6B--IN)") (class "Default")
      (node (ref "IC6") (pin "6") (pinfunction "-IN_6") (pintype "input"))
      (node (ref "IC6") (pin "7") (pinfunction "OUT_7") (pintype "output"))
      (node (ref "R33") (pin "3") (pinfunction "E_3") (pintype "passive"))
      (node (ref "R34") (pin "2") (pinfunction "2_2") (pintype "passive"))
      (node (ref "R39") (pin "1") (pinfunction "1_1") (pintype "passive"))
    )
    (net (code "63") (name "Net-(IC6C--IN)") (class "Default")
      (node (ref "IC6") (pin "8") (pinfunction "OUT_8") (pintype "output"))
      (node (ref "IC6") (pin "9") (pinfunction "-IN_9") (pintype "input"))
      (node (ref "R35") (pin "3") (pinfunction "E_3") (pintype "passive"))
      (node (ref "R36") (pin "2") (pinfunction "2_2") (pintype "passive"))
      (node (ref "R40") (pin "1") (pinfunction "1_1") (pintype "passive"))
    )
    (net (code "64") (name "Net-(IC6D--IN)") (class "Default")
      (node (ref "D8") (pin "A") (pinfunction "A_A") (pintype "passive"))
      (node (ref "IC6") (pin "13") (pinfunction "-IN_13") (pintype "input"))
      (node (ref "IC6") (pin "14") (pinfunction "OUT_14") (pintype "output"))
    )
    (net (code "65") (name "Net-(J1-PadP$3)") (class "Default")
      (node (ref "J1") (pin "P$3") (pinfunction "P$3_P$3") (pintype "bidirectional"))
      (node (ref "J1") (pin "P$4") (pinfunction "P$4_P$4") (pintype "bidirectional"))
      (node (ref "R30") (pin "1") (pinfunction "1_1") (pintype "passive"))
    )
    (net (code "66") (name "Net-(J2-PadP$3)") (class "Default")
      (node (ref "J2") (pin "P$3") (pinfunction "P$3_P$3") (pintype "bidirectional"))
      (node (ref "J2") (pin "P$4") (pinfunction "P$4_P$4") (pintype "bidirectional"))
      (node (ref "R32") (pin "1") (pinfunction "1_1") (pintype "passive"))
    )
    (net (code "67") (name "Net-(J3-PadP$3)") (class "Default")
      (node (ref "J3") (pin "P$3") (pinfunction "P$3_P$3") (pintype "bidirectional"))
      (node (ref "J3") (pin "P$4") (pinfunction "P$4_P$4") (pintype "bidirectional"))
      (node (ref "R34") (pin "1") (pinfunction "1_1") (pintype "passive"))
    )
    (net (code "68") (name "Net-(J4-PadP$3)") (class "Default")
      (node (ref "J4") (pin "P$3") (pinfunction "P$3_P$3") (pintype "bidirectional"))
      (node (ref "J4") (pin "P$4") (pinfunction "P$4_P$4") (pintype "bidirectional"))
      (node (ref "R36") (pin "1") (pinfunction "1_1") (pintype "passive"))
    )
    (net (code "69") (name "Net-(RV1-1)") (class "Default")
      (node (ref "R25") (pin "2") (pinfunction "2_2") (pintype "passive"))
      (node (ref "RV1") (pin "R1") (pinfunction "1_R1") (pintype "passive"))
    )
    (net (code "70") (name "Net-(RV2-1)") (class "Default")
      (node (ref "R26") (pin "2") (pinfunction "2_2") (pintype "passive"))
      (node (ref "RV2") (pin "R1") (pinfunction "1_R1") (pintype "passive"))
    )
    (net (code "71") (name "Net-(RV3-1)") (class "Default")
      (node (ref "R27") (pin "2") (pinfunction "2_2") (pintype "passive"))
      (node (ref "RV3") (pin "R1") (pinfunction "1_R1") (pintype "passive"))
    )
  )
)
